# Connections.net
KiCad netlist of a schematic drawn in Altium Designer
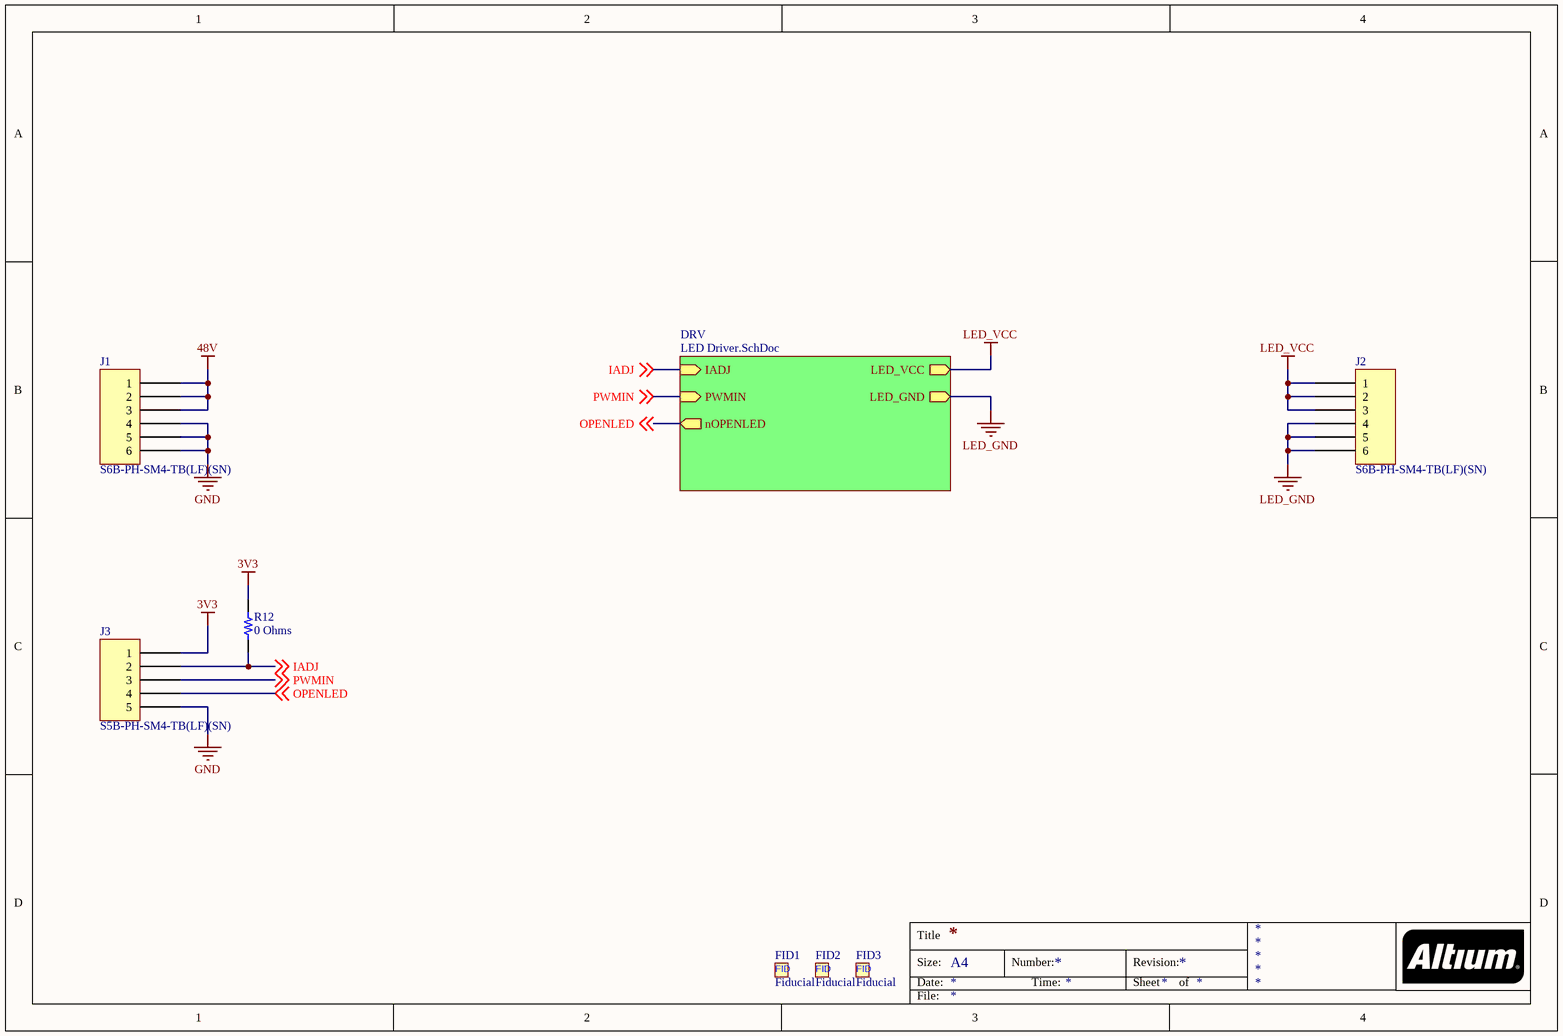
[diagram p0: Connections.SchDoc]

(export (version "E")
  (design (tool "Eeschema 10.0.6"))
  (components
    (comp (ref "FID1") (value "Fiducial") (footprint "Fiducial") (libsource (lib "Useful") (part "Fiducial")))
    (comp (ref "FID2") (value "Fiducial") (footprint "Fiducial") (libsource (lib "Useful") (part "Fiducial")))
    (comp (ref "FID3") (value "Fiducial") (footprint "Fiducial") (libsource (lib "Useful") (part "Fiducial")))
    (comp (ref "J1")
      (value "S6B-PH-SM4-TB(LF)(SN)")
      (footprint "JST S6B-PH-SM4-TB")
      (description "CONN HEADER SMD R/A 6POS 2MM")
      (fields (field (name "MANUFACTURER") "JST Sales America Inc."))
      (libsource (lib "Celestial Altium Library - altium_library") (part "6 Pin"))
    )
    (comp (ref "J2")
      (value "S6B-PH-SM4-TB(LF)(SN)")
      (footprint "JST S6B-PH-SM4-TB")
      (description "CONN HEADER SMD R/A 6POS 2MM")
      (fields (field (name "MANUFACTURER") "JST Sales America Inc."))
      (libsource (lib "") (part "6 Pin_1"))
    )
    (comp (ref "J3")
      (value "S5B-PH-SM4-TB(LF)(SN)")
      (footprint "JST S5B-PH-SM4-TB")
      (description "CONN HEADER SMD R/A 5POS 2MM")
      (fields (field (name "MANUFACTURER") "JST Sales America Inc."))
      (libsource (lib "Celestial Altium Library - altium_library") (part "5 Pin"))
    )
    (comp (ref "R12")
      (value "0 Ohms")
      (footprint "RES 0603_1608")
      (description "RES SMD 0 OHM JUMPER 1/10W 0603")
      (fields
        (field (name "PART NUMBER") "ERJ-3GEY0R00V")
        (field (name "MANUFACTURER") "Panasonic Electronic Components")
      )
      (libsource (lib "Celestial Altium Library - altium_library") (part "Resistor"))
    )
  )
  (nets
    (net (code "1") (name "3V3") (class "Default")
      (node (ref "J3") (pin "1") (pinfunction "1_1") (pintype "passive"))
      (node (ref "R12") (pin "2") (pinfunction "2_2") (pintype "passive"))
    )
    (net (code "2") (name "48V") (class "Default")
      (node (ref "J1") (pin "1") (pinfunction "1_1") (pintype "passive"))
      (node (ref "J1") (pin "2") (pinfunction "2_2") (pintype "passive"))
      (node (ref "J1") (pin "3") (pinfunction "3_3") (pintype "passive"))
    )
    (net (code "3") (name "GND") (class "Default")
      (node (ref "J1") (pin "4") (pinfunction "4_4") (pintype "passive"))
      (node (ref "J1") (pin "5") (pinfunction "5_5") (pintype "passive"))
      (node (ref "J1") (pin "6") (pinfunction "6_6") (pintype "passive"))
      (node (ref "J3") (pin "5") (pinfunction "5_5") (pintype "passive"))
    )
    (net (code "4") (name "IADJ") (class "Default")
      (node (ref "J3") (pin "2") (pinfunction "2_2") (pintype "passive"))
      (node (ref "R12") (pin "1") (pinfunction "1_1") (pintype "passive"))
    )
    (net (code "5") (name "LED_GND") (class "Default")
      (node (ref "J2") (pin "4") (pinfunction "4_4") (pintype "passive"))
      (node (ref "J2") (pin "5") (pinfunction "5_5") (pintype "passive"))
      (node (ref "J2") (pin "6") (pinfunction "6_6") (pintype "passive"))
    )
    (net (code "6") (name "LED_VCC") (class "Default")
      (node (ref "J2") (pin "1") (pinfunction "1_1") (pintype "passive"))
      (node (ref "J2") (pin "2") (pinfunction "2_2") (pintype "passive"))
      (node (ref "J2") (pin "3") (pinfunction "3_3") (pintype "passive"))
    )
    (net (code "7") (name "OPENLED") (class "Default")
      (node (ref "J3") (pin "4") (pinfunction "4_4") (pintype "passive"))
    )
    (net (code "8") (name "PWMIN") (class "Default")
      (node (ref "J3") (pin "3") (pinfunction "3_3") (pintype "passive"))
    )
  )
)
